# 100_POWER.net
KiCad netlist of a schematic drawn in Altium Designer
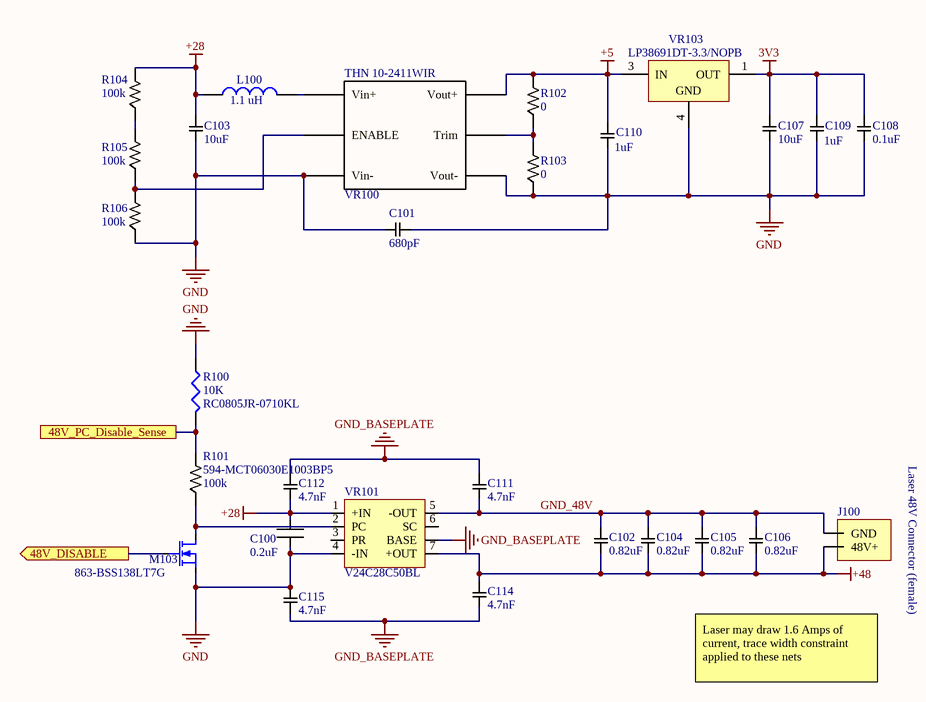
[diagram p0: 100_POWER.SchDoc]

(export (version "E")
  (design (tool "Eeschema 10.0.6"))
  (components
    (comp (ref "C100")
      (value "0.2uF")
      (footprint "CAA572C0G2J204J640LH")
      (description "0.2uF capacitor, high voltage")
      (fields (field (name "Comment") "0.2uF Capactor, high voltage"))
      (libsource (lib "OASIS_COMPONENTS_SYMBOLS") (part "CAA572C0G2J204J640LH"))
    )
    (comp (ref "C101")
      (value "680pF")
      (footprint "Imperial1808_CAP")
      (description "680pF Cap for EMI suppresion on 5V regulator")
      (fields (field (name "Comment") "680pF Cap"))
      (libsource (lib "OASIS_COMPONENTS_SYMBOLS") (part "C1808C681KHRACTU"))
    )
    (comp (ref "C102")
      (value "0.82uF")
      (footprint "IMPERIAL1206_CAPACITOR")
      (description "0.82 uF Capacitor for creating output capacitance on 48V converter")
      (fields
        (field (name "MANUFACTURER PART NUMBER") "C1206X824J1RACAUTO")
        (field (name "MANUFACTURER") "KEMET")
      )
      (libsource (lib "OASIS_COMPONENTS_SYMBOLS") (part "C1206X824J1RACAUTO"))
    )
    (comp (ref "C103")
      (value "10uF")
      (footprint "Imperial1210_Cap")
      (description "10 uF Capacitor for EMI supression on 5V regulator")
      (fields (field (name "Comment") "10uF Capacitor"))
      (libsource (lib "OASIS_COMPONENTS_SYMBOLS") (part "CNA6P1X7R1H106K250AE"))
    )
    (comp (ref "C104")
      (value "0.82uF")
      (footprint "IMPERIAL1206_CAPACITOR")
      (description "0.82 uF Capacitor for creating output capacitance on 48V converter")
      (fields
        (field (name "MANUFACTURER PART NUMBER") "C1206X824J1RACAUTO")
        (field (name "MANUFACTURER") "KEMET")
      )
      (libsource (lib "OASIS_COMPONENTS_SYMBOLS") (part "C1206X824J1RACAUTO"))
    )
    (comp (ref "C105")
      (value "0.82uF")
      (footprint "IMPERIAL1206_CAPACITOR")
      (description "0.82 uF Capacitor for creating output capacitance on 48V converter")
      (fields
        (field (name "MANUFACTURER PART NUMBER") "C1206X824J1RACAUTO")
        (field (name "MANUFACTURER") "KEMET")
      )
      (libsource (lib "OASIS_COMPONENTS_SYMBOLS") (part "C1206X824J1RACAUTO"))
    )
    (comp (ref "C106")
      (value "0.82uF")
      (footprint "IMPERIAL1206_CAPACITOR")
      (description "0.82 uF Capacitor for creating output capacitance on 48V converter")
      (fields
        (field (name "MANUFACTURER PART NUMBER") "C1206X824J1RACAUTO")
        (field (name "MANUFACTURER") "KEMET")
      )
      (libsource (lib "OASIS_COMPONENTS_SYMBOLS") (part "C1206X824J1RACAUTO"))
    )
    (comp (ref "C107")
      (value "10uF")
      (footprint "IMPERIAL1206_CAPACITOR")
      (description "10 uF Capacitor, non-polar")
      (fields
        (field (name "MANUFACTURER PART NUMBER") "C1206X106K8RACAUTO")
        (field (name "MANUFACTURER") "KEMET")
      )
      (libsource (lib "OASIS_COMPONENTS_SYMBOLS") (part "C1206X106K8RACAUTO"))
    )
    (comp (ref "C108")
      (value "0.1uF")
      (footprint "IMPERIAL0603_Capacitor")
      (description "0.1uF Capacitor, Non Polarized Chip Cap")
      (fields (field (name "Comment") "0.1uF Capacitor"))
      (libsource (lib "OASIS_COMPONENTS_SYMBOLS") (part "VJ0603Y104MXQPW1BC"))
    )
    (comp (ref "C109")
      (value "1uF")
      (footprint "IMPERIAL0603_Capacitor")
      (description "1 uF Capacitor")
      (libsource (lib "OASIS_COMPONENTS_SYMBOLS") (part "TMK107BLD105KA-T"))
    )
    (comp (ref "C110")
      (value "1uF")
      (footprint "IMPERIAL0603_Capacitor")
      (description "1 uF Capacitor")
      (libsource (lib "OASIS_COMPONENTS_SYMBOLS") (part "TMK107BLD105KA-T"))
    )
    (comp (ref "C111")
      (value "4.7nF")
      (footprint "IMPERIAL0603_Capacitor")
      (description "4.7nF soft terminated MLCC capacitor for 48V emi filtering")
      (fields (field (name "Comment") "4.7nF Capacitor"))
      (libsource (lib "OASIS_COMPONENTS_SYMBOLS") (part "CGA3E2X8R2A472K080AE"))
    )
    (comp (ref "C112")
      (value "4.7nF")
      (footprint "IMPERIAL0603_Capacitor")
      (description "4.7nF soft terminated MLCC capacitor for 48V emi filtering")
      (fields (field (name "Comment") "4.7nF Capacitor"))
      (libsource (lib "OASIS_COMPONENTS_SYMBOLS") (part "CGA3E2X8R2A472K080AE"))
    )
    (comp (ref "C114")
      (value "4.7nF")
      (footprint "IMPERIAL0603_Capacitor")
      (description "4.7nF soft terminated MLCC capacitor for 48V emi filtering")
      (fields (field (name "Comment") "4.7nF Capacitor"))
      (libsource (lib "OASIS_COMPONENTS_SYMBOLS") (part "CGA3E2X8R2A472K080AE"))
    )
    (comp (ref "C115")
      (value "4.7nF")
      (footprint "IMPERIAL0603_Capacitor")
      (description "4.7nF soft terminated MLCC capacitor for 48V emi filtering")
      (fields (field (name "Comment") "4.7nF Capacitor"))
      (libsource (lib "OASIS_COMPONENTS_SYMBOLS") (part "CGA3E2X8R2A472K080AE"))
    )
    (comp (ref "J100")
      (value "LaserHeader")
      (footprint "MOLEX 2X1 LATCH HEADER")
      (description "2 pin molex connector for connecting laser to 48Vdc")
      (libsource (lib "OASIS_COMPONENTS_SYMBOLS") (part "LaserHeader"))
    )
    (comp (ref "L100")
      (value "1.1 uH")
      (footprint "XAL6020-112ME_")
      (description "1.1uH inductor for EMI suppresion on 5V regulator")
      (fields (field (name "Comment") "1.1uH Inductor"))
      (libsource (lib "OASIS_COMPONENTS_SYMBOLS") (part "XAL6020-112MEB"))
    )
    (comp (ref "M103")
      (value "BSS138LT7G")
      (footprint "SOT95P245X110-3N")
      (description "N-MOSFET for logic level switching")
      (fields (field (name "SUPPLIER PART NUMBER 1") "863-BSS138LT7G"))
      (libsource (lib "OASIS_COMPONENTS_SYMBOLS") (part "BSS138LT7G"))
    )
    (comp (ref "R100")
      (value "RC0805JR-0710KL")
      (footprint "Imperial0805_RES")
      (description "10K resistor, 1/8W, 0805 Imperial")
      (fields (field (name "ALTIUM_VALUE") "10K"))
      (libsource (lib "OASIS_COMPONENTS_SYMBOLS") (part "RC0805JR-0710KL"))
    )
    (comp (ref "R101")
      (value "100k")
      (footprint "Imperial0603_RES")
      (description "100 kOhm Resistor")
      (fields
        (field (name "SUPPLIER PART NUMBER 1") "594-MCT06030E1003BP5")
        (field (name "Comment") "MCT06030E1003BP500")
      )
      (libsource (lib "OASIS_COMPONENTS_SYMBOLS") (part "MCT06030E1003BP500"))
    )
    (comp (ref "R102")
      (value "0")
      (footprint "Imperial0603_RES")
      (description "Placeholder 0 Ohm Link.")
      (fields (field (name "Comment") "0 Ohm Link"))
      (libsource (lib "OASIS_COMPONENTS_SYMBOLS") (part "0_Ohm_Link"))
    )
    (comp (ref "R103")
      (value "0")
      (footprint "Imperial0603_RES")
      (description "Placeholder 0 Ohm Link.")
      (fields (field (name "Comment") "0 Ohm Link"))
      (libsource (lib "OASIS_COMPONENTS_SYMBOLS") (part "0_Ohm_Link"))
    )
    (comp (ref "R104")
      (value "100k")
      (footprint "Imperial0603_RES")
      (description "100 kOhm Resistor")
      (fields (field (name "Comment") "MCT06030E1003BP500"))
      (libsource (lib "OASIS_COMPONENTS_SYMBOLS") (part "MCT06030E1003BP500"))
    )
    (comp (ref "R105")
      (value "100k")
      (footprint "Imperial0603_RES")
      (description "100 kOhm Resistor")
      (fields (field (name "Comment") "MCT06030E1003BP500"))
      (libsource (lib "OASIS_COMPONENTS_SYMBOLS") (part "MCT06030E1003BP500"))
    )
    (comp (ref "R106")
      (value "100k")
      (footprint "Imperial0603_RES")
      (description "100 kOhm Resistor")
      (fields (field (name "Comment") "MCT06030E1003BP500"))
      (libsource (lib "OASIS_COMPONENTS_SYMBOLS") (part "MCT06030E1003BP500"))
    )
    (comp (ref "VR100")
      (value "28 to 5V switching converter")
      (footprint "THN 30-2411WI-A1")
      (description "28V to 5V converter")
      (fields (field (name "MANUFACTURE PART NO") "THN 10-2411WIR"))
      (libsource (lib "OASIS_COMPONENTS_SYMBOLS") (part "THN 10-2411WIR"))
    )
    (comp (ref "VR101")
      (value "V24C28C50BL")
      (footprint "V24C48C50BL_tht")
      (description "28V to 48V converter, 50W")
      (libsource (lib "OASIS_COMPONENTS_SYMBOLS") (part "V24C28C50BL"))
    )
    (comp (ref "VR103")
      (value "LP38691DT-3.3/NOPB")
      (footprint "NDP0003B_N")
      (fields
        (field (name "MANUFACTURER") "Texas Instruments")
        (field (name "PARTNUMBER") "LP38691DT-3.3/NOPB")
      )
      (libsource (lib "OASIS_COMPONENTS_SYMBOLS") (part "CMP-0062-00443-4"))
    )
  )
  (nets
    (net (code "1") (name "+5") (class "Default")
      (node (ref "C110") (pin "2") (pinfunction "2_2") (pintype "passive"))
      (node (ref "R102") (pin "1") (pinfunction "1_1") (pintype "passive"))
      (node (ref "VR100") (pin "3") (pinfunction "Vout+_3") (pintype "passive"))
      (node (ref "VR103") (pin "3") (pinfunction "IN_3") (pintype "power_in"))
    )
    (net (code "2") (name "+28") (class "Default")
      (node (ref "C100") (pin "2") (pinfunction "2_2") (pintype "passive"))
      (node (ref "C103") (pin "2") (pinfunction "2_2") (pintype "passive"))
      (node (ref "C112") (pin "1") (pinfunction "1_1") (pintype "passive"))
      (node (ref "L100") (pin "1") (pinfunction "1_1") (pintype "passive"))
      (node (ref "R104") (pin "1") (pinfunction "1_1") (pintype "passive"))
      (node (ref "VR101") (pin "1") (pinfunction "+IN_1") (pintype "passive"))
    )
    (net (code "3") (name "+48") (class "Default")
      (node (ref "C102") (pin "1") (pinfunction "1_1") (pintype "passive"))
      (node (ref "C104") (pin "1") (pinfunction "1_1") (pintype "passive"))
      (node (ref "C105") (pin "1") (pinfunction "1_1") (pintype "passive"))
      (node (ref "C106") (pin "1") (pinfunction "1_1") (pintype "passive"))
      (node (ref "C114") (pin "2") (pinfunction "2_2") (pintype "passive"))
      (node (ref "J100") (pin "1") (pinfunction "48V+_1") (pintype "passive"))
      (node (ref "VR101") (pin "7") (pinfunction "+OUT_7") (pintype "passive"))
    )
    (net (code "4") (name "/48V_DISABLE") (class "Default")
      (node (ref "M103") (pin "1") (pinfunction "G_1") (pintype "passive"))
    )
    (net (code "5") (name "/48V_PC_Disable_Sense") (class "Default")
      (node (ref "R100") (pin "2") (pinfunction "2_2") (pintype "passive"))
      (node (ref "R101") (pin "1") (pinfunction "1_1") (pintype "passive"))
    )
    (net (code "6") (name "/GND_48V") (class "Default")
      (node (ref "C102") (pin "2") (pinfunction "2_2") (pintype "passive"))
      (node (ref "C104") (pin "2") (pinfunction "2_2") (pintype "passive"))
      (node (ref "C105") (pin "2") (pinfunction "2_2") (pintype "passive"))
      (node (ref "C106") (pin "2") (pinfunction "2_2") (pintype "passive"))
      (node (ref "C111") (pin "1") (pinfunction "1_1") (pintype "passive"))
      (node (ref "J100") (pin "2") (pinfunction "GND_2") (pintype "passive"))
      (node (ref "VR101") (pin "5") (pinfunction "-OUT_5") (pintype "passive"))
    )
    (net (code "7") (name "3V3") (class "Default")
      (node (ref "C107") (pin "2") (pinfunction "2_2") (pintype "passive"))
      (node (ref "C108") (pin "2") (pinfunction "2_2") (pintype "passive"))
      (node (ref "C109") (pin "2") (pinfunction "2_2") (pintype "passive"))
      (node (ref "VR103") (pin "1") (pinfunction "OUT_1") (pintype "power_in"))
    )
    (net (code "8") (name "GND") (class "Default")
      (node (ref "C100") (pin "1") (pinfunction "1_1") (pintype "passive"))
      (node (ref "C101") (pin "1") (pinfunction "1_1") (pintype "passive"))
      (node (ref "C101") (pin "2") (pinfunction "2_2") (pintype "passive"))
      (node (ref "C103") (pin "1") (pinfunction "1_1") (pintype "passive"))
      (node (ref "C107") (pin "1") (pinfunction "1_1") (pintype "passive"))
      (node (ref "C108") (pin "1") (pinfunction "1_1") (pintype "passive"))
      (node (ref "C109") (pin "1") (pinfunction "1_1") (pintype "passive"))
      (node (ref "C110") (pin "1") (pinfunction "1_1") (pintype "passive"))
      (node (ref "C115") (pin "1") (pinfunction "1_1") (pintype "passive"))
      (node (ref "M103") (pin "2") (pinfunction "S_2") (pintype "passive"))
      (node (ref "R100") (pin "1") (pinfunction "1_1") (pintype "passive"))
      (node (ref "R103") (pin "2") (pinfunction "2_2") (pintype "passive"))
      (node (ref "R106") (pin "2") (pinfunction "2_2") (pintype "passive"))
      (node (ref "VR100") (pin "2") (pinfunction "Vin-_2") (pintype "passive"))
      (node (ref "VR100") (pin "5") (pinfunction "Vout-_5") (pintype "passive"))
      (node (ref "VR101") (pin "4") (pinfunction "-IN_4") (pintype "passive"))
      (node (ref "VR103") (pin "4") (pinfunction "GND_4") (pintype "power_in"))
    )
    (net (code "9") (name "GND_BASEPLATE") (class "Default")
      (node (ref "C111") (pin "2") (pinfunction "2_2") (pintype "passive"))
      (node (ref "C112") (pin "2") (pinfunction "2_2") (pintype "passive"))
      (node (ref "C114") (pin "1") (pinfunction "1_1") (pintype "passive"))
      (node (ref "C115") (pin "2") (pinfunction "2_2") (pintype "passive"))
      (node (ref "VR101") (pin "BASE") (pinfunction "BASE_BASE") (pintype "passive"))
    )
    (net (code "10") (name "Net-(M103-D)") (class "Default")
      (node (ref "M103") (pin "3") (pinfunction "D_3") (pintype "passive"))
      (node (ref "R101") (pin "2") (pinfunction "2_2") (pintype "passive"))
      (node (ref "VR101") (pin "2") (pinfunction "PC_2") (pintype "passive"))
    )
    (net (code "11") (name "Net-(R104-Pad2)") (class "Default")
      (node (ref "R104") (pin "2") (pinfunction "2_2") (pintype "passive"))
      (node (ref "R105") (pin "1") (pinfunction "1_1") (pintype "passive"))
    )
    (net (code "12") (name "Net-(VR100-ENABLE)") (class "Default")
      (node (ref "R105") (pin "2") (pinfunction "2_2") (pintype "passive"))
      (node (ref "R106") (pin "1") (pinfunction "1_1") (pintype "passive"))
      (node (ref "VR100") (pin "6") (pinfunction "ENABLE_6") (pintype "passive"))
    )
    (net (code "13") (name "Net-(VR100-Trim)") (class "Default")
      (node (ref "R102") (pin "2") (pinfunction "2_2") (pintype "passive"))
      (node (ref "R103") (pin "1") (pinfunction "1_1") (pintype "passive"))
      (node (ref "VR100") (pin "4") (pinfunction "Trim_4") (pintype "passive"))
    )
    (net (code "14") (name "Net-(VR100-Vin+)") (class "Default")
      (node (ref "L100") (pin "2") (pinfunction "2_2") (pintype "passive"))
      (node (ref "VR100") (pin "1") (pinfunction "Vin+_1") (pintype "passive"))
    )
    (net (code "15") (name "unconnected-(VR101-PR-Pad3)") (class "Default")
      (node (ref "VR101") (pin "3") (pinfunction "PR_3") (pintype "passive"))
    )
    (net (code "16") (name "unconnected-(VR101-SC-Pad6)") (class "Default")
      (node (ref "VR101") (pin "6") (pinfunction "SC_6") (pintype "passive"))
    )
  )
)
